# Qiao.net
KiCad netlist of a schematic drawn in Altium Designer
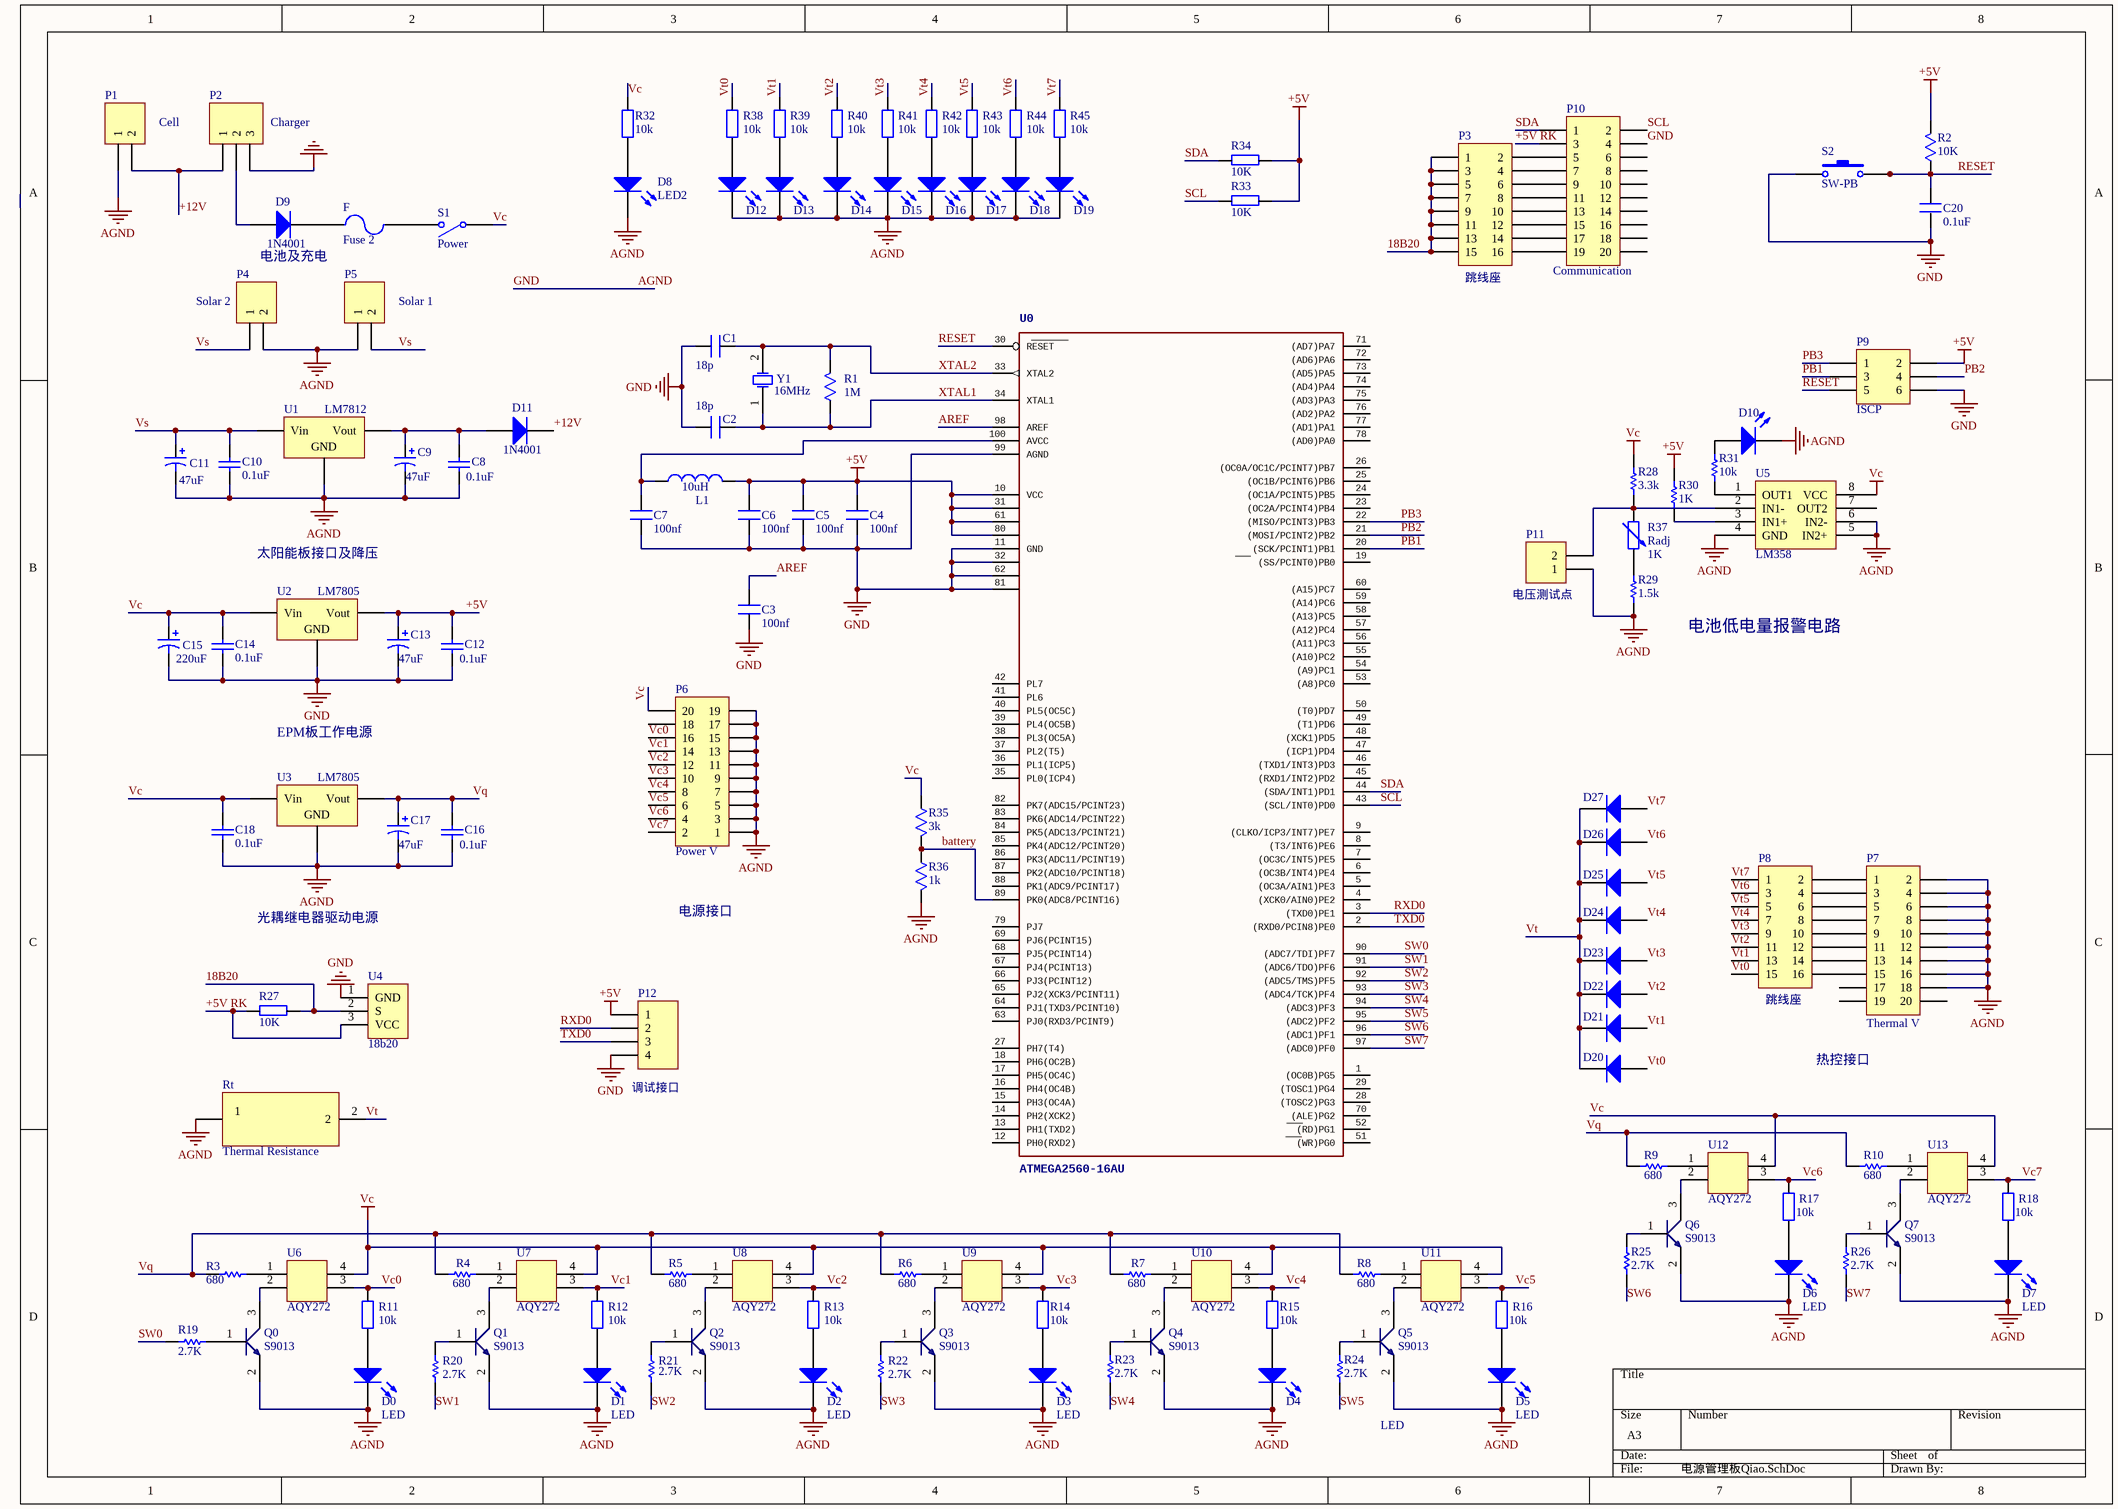
[diagram p0: 电源管理板Qiao.SchDoc]

(export (version "E")
  (design (tool "Eeschema 10.0.6"))
  (components
    (comp (ref "C1") (value "18p") (footprint "CAPC3216M") (libsource (lib "STM32封装库") (part "C_1")))
    (comp (ref "C2") (value "18p") (footprint "CAPC3216M") (libsource (lib "STM32封装库") (part "C_1")))
    (comp (ref "C3") (value "100nf") (footprint "CAPC3216M") (libsource (lib "STM32封装库") (part "C")))
    (comp (ref "C4") (value "100nf") (footprint "CAPC3216M") (libsource (lib "STM32封装库") (part "C")))
    (comp (ref "C5") (value "100nf") (footprint "CAPC3216M") (libsource (lib "STM32封装库") (part "C")))
    (comp (ref "C6") (value "100nf") (footprint "CAPC3216M") (libsource (lib "STM32封装库") (part "C")))
    (comp (ref "C7") (value "100nf") (footprint "CAPC3216M") (libsource (lib "STM32封装库") (part "C")))
    (comp (ref "C8")
      (value "0.1uF")
      (footprint "CAPC3216M")
      (description "0.1uf")
      (fields (field (name "PUBLISHER") "Altium Limited"))
      (libsource (lib "Miscellaneous Devices") (part "Cap Semi"))
    )
    (comp (ref "C9")
      (value "47uF")
      (footprint "25V47uF")
      (description "47uf")
      (fields (field (name "Comment") "25V47uF") (field (name "PUBLISHER") "Altium Limited"))
      (libsource (lib "Miscellaneous Devices") (part "Cap Pol3"))
    )
    (comp (ref "C10")
      (value "0.1uF")
      (footprint "CAPC3216M")
      (description "0.1uf")
      (fields (field (name "PUBLISHER") "Altium Limited"))
      (libsource (lib "电源管理板") (part "Cap"))
    )
    (comp (ref "C11")
      (value "47uF")
      (footprint "25V47uF")
      (description "47uf")
      (fields (field (name "Comment") "25V47uF") (field (name "PUBLISHER") "Altium Limited"))
      (libsource (lib "Miscellaneous Devices") (part "Cap Pol3"))
    )
    (comp (ref "C12")
      (value "0.1uF")
      (footprint "CAPC3216M")
      (description "0.1uf")
      (fields (field (name "PUBLISHER") "Altium Limited"))
      (libsource (lib "Miscellaneous Devices") (part "Cap Semi"))
    )
    (comp (ref "C13")
      (value "47uF")
      (footprint "25V47uF")
      (description "10uf")
      (fields (field (name "Comment") "25V47uF") (field (name "PUBLISHER") "Altium Limited"))
      (libsource (lib "Miscellaneous Devices") (part "Cap Pol3"))
    )
    (comp (ref "C14")
      (value "0.1uF")
      (footprint "CAPC3216M")
      (description "0.1uf")
      (fields (field (name "PUBLISHER") "Altium Limited"))
      (libsource (lib "Miscellaneous Devices") (part "Cap"))
    )
    (comp (ref "C15")
      (value "220uF")
      (footprint "25V47uF")
      (description "10uf")
      (fields (field (name "Comment") "50V220uF") (field (name "PUBLISHER") "Altium Limited"))
      (libsource (lib "Miscellaneous Devices") (part "Cap Pol3"))
    )
    (comp (ref "C16")
      (value "0.1uF")
      (footprint "CAPC3216M")
      (description "0.1uf")
      (fields (field (name "PUBLISHER") "Altium Limited"))
      (libsource (lib "Miscellaneous Devices") (part "Cap Semi"))
    )
    (comp (ref "C17")
      (value "47uF")
      (footprint "25V47uF")
      (description "10uf")
      (fields (field (name "Comment") "25V47uF") (field (name "PUBLISHER") "Altium Limited"))
      (libsource (lib "Miscellaneous Devices") (part "Cap Pol3"))
    )
    (comp (ref "C18")
      (value "0.1uF")
      (footprint "CAPC3216M")
      (description "0.1uf")
      (fields (field (name "PUBLISHER") "Altium Limited"))
      (libsource (lib "Miscellaneous Devices") (part "Cap"))
    )
    (comp (ref "C20") (value "0.1uF") (footprint "CAPC3216M") (libsource (lib "STM32封装库") (part "C_3")))
    (comp (ref "D0")
      (value "LED")
      (footprint "LED")
      (description "Typical RED, GREEN, YELLOW, AMBER GaAs LED")
      (fields (field (name "PUBLISHER") "Altium Limited"))
      (libsource (lib "Miscellaneous Devices") (part "LED2"))
    )
    (comp (ref "D1")
      (value "LED")
      (footprint "LED")
      (description "Typical RED, GREEN, YELLOW, AMBER GaAs LED")
      (fields (field (name "PUBLISHER") "Altium Limited"))
      (libsource (lib "Miscellaneous Devices") (part "LED2"))
    )
    (comp (ref "D2")
      (value "LED")
      (footprint "LED")
      (description "Typical RED, GREEN, YELLOW, AMBER GaAs LED")
      (fields (field (name "PUBLISHER") "Altium Limited"))
      (libsource (lib "Miscellaneous Devices") (part "LED2"))
    )
    (comp (ref "D3")
      (value "LED")
      (footprint "LED")
      (description "Typical RED, GREEN, YELLOW, AMBER GaAs LED")
      (fields (field (name "PUBLISHER") "Altium Limited"))
      (libsource (lib "Miscellaneous Devices") (part "LED2"))
    )
    (comp (ref "D4")
      (value "LED")
      (footprint "LED")
      (description "Typical RED, GREEN, YELLOW, AMBER GaAs LED")
      (fields (field (name "PUBLISHER") "Altium Limited"))
      (libsource (lib "Miscellaneous Devices") (part "LED2"))
    )
    (comp (ref "D5")
      (value "LED")
      (footprint "LED")
      (description "Typical RED, GREEN, YELLOW, AMBER GaAs LED")
      (fields (field (name "PUBLISHER") "Altium Limited"))
      (libsource (lib "Miscellaneous Devices") (part "LED2"))
    )
    (comp (ref "D6")
      (value "LED")
      (footprint "LED")
      (description "Typical RED, GREEN, YELLOW, AMBER GaAs LED")
      (fields (field (name "PUBLISHER") "Altium Limited"))
      (libsource (lib "Miscellaneous Devices") (part "LED2"))
    )
    (comp (ref "D7")
      (value "LED")
      (footprint "LED")
      (description "Typical RED, GREEN, YELLOW, AMBER GaAs LED")
      (fields (field (name "PUBLISHER") "Altium Limited"))
      (libsource (lib "Miscellaneous Devices") (part "LED2"))
    )
    (comp (ref "D8")
      (value "LED2")
      (footprint "DIPLED")
      (description "Typical RED, GREEN, YELLOW, AMBER GaAs LED")
      (fields (field (name "PUBLISHER") "Altium Limited"))
      (libsource (lib "Miscellaneous Devices") (part "LED2"))
    )
    (comp (ref "D9")
      (value "1N4001")
      (footprint "SMB")
      (description "1 Amp General Purpose Rectifier")
      (fields (field (name "PUBLISHER") "Altium Limited"))
      (libsource (lib "Miscellaneous Devices") (part "Diode 1N4001"))
    )
    (comp (ref "D10") (value "LED") (footprint "DIPLED") (libsource (lib "常用元件库") (part "LED")))
    (comp (ref "D11")
      (value "1N4001")
      (footprint "SMB")
      (description "1 Amp General Purpose Rectifier")
      (fields (field (name "PUBLISHER") "Altium Limited"))
      (libsource (lib "Miscellaneous Devices") (part "Diode 1N4001"))
    )
    (comp (ref "D12")
      (value "LED")
      (footprint "LED")
      (description "Typical RED, GREEN, YELLOW, AMBER GaAs LED")
      (fields (field (name "PUBLISHER") "Altium Limited"))
      (libsource (lib "Miscellaneous Devices") (part "LED2"))
    )
    (comp (ref "D13")
      (value "LED")
      (footprint "LED")
      (description "Typical RED, GREEN, YELLOW, AMBER GaAs LED")
      (fields (field (name "PUBLISHER") "Altium Limited"))
      (libsource (lib "Miscellaneous Devices") (part "LED2"))
    )
    (comp (ref "D14")
      (value "LED")
      (footprint "LED")
      (description "Typical RED, GREEN, YELLOW, AMBER GaAs LED")
      (fields (field (name "PUBLISHER") "Altium Limited"))
      (libsource (lib "Miscellaneous Devices") (part "LED2"))
    )
    (comp (ref "D15")
      (value "LED")
      (footprint "LED")
      (description "Typical RED, GREEN, YELLOW, AMBER GaAs LED")
      (fields (field (name "PUBLISHER") "Altium Limited"))
      (libsource (lib "Miscellaneous Devices") (part "LED2"))
    )
    (comp (ref "D16")
      (value "LED")
      (footprint "LED")
      (description "Typical RED, GREEN, YELLOW, AMBER GaAs LED")
      (fields (field (name "PUBLISHER") "Altium Limited"))
      (libsource (lib "Miscellaneous Devices") (part "LED2"))
    )
    (comp (ref "D17")
      (value "LED")
      (footprint "LED")
      (description "Typical RED, GREEN, YELLOW, AMBER GaAs LED")
      (fields (field (name "PUBLISHER") "Altium Limited"))
      (libsource (lib "Miscellaneous Devices") (part "LED2"))
    )
    (comp (ref "D18")
      (value "LED")
      (footprint "LED")
      (description "Typical RED, GREEN, YELLOW, AMBER GaAs LED")
      (fields (field (name "PUBLISHER") "Altium Limited"))
      (libsource (lib "Miscellaneous Devices") (part "LED2"))
    )
    (comp (ref "D19")
      (value "LED")
      (footprint "LED")
      (description "Typical RED, GREEN, YELLOW, AMBER GaAs LED")
      (fields (field (name "PUBLISHER") "Altium Limited"))
      (libsource (lib "Miscellaneous Devices") (part "LED2"))
    )
    (comp (ref "D20")
      (value "1N4001")
      (footprint "SMB")
      (description "1 Amp General Purpose Rectifier")
      (fields (field (name "PUBLISHER") "Altium Limited"))
      (libsource (lib "Miscellaneous Devices") (part "Diode 1N4001"))
    )
    (comp (ref "D21")
      (value "1N4001")
      (footprint "SMB")
      (description "1 Amp General Purpose Rectifier")
      (fields (field (name "PUBLISHER") "Altium Limited"))
      (libsource (lib "Miscellaneous Devices") (part "Diode 1N4001"))
    )
    (comp (ref "D22")
      (value "1N4001")
      (footprint "SMB")
      (description "1 Amp General Purpose Rectifier")
      (fields (field (name "PUBLISHER") "Altium Limited"))
      (libsource (lib "Miscellaneous Devices") (part "Diode 1N4001"))
    )
    (comp (ref "D23")
      (value "1N4001")
      (footprint "SMB")
      (description "1 Amp General Purpose Rectifier")
      (fields (field (name "PUBLISHER") "Altium Limited"))
      (libsource (lib "Miscellaneous Devices") (part "Diode 1N4001"))
    )
    (comp (ref "D24")
      (value "1N4001")
      (footprint "SMB")
      (description "1 Amp General Purpose Rectifier")
      (fields (field (name "PUBLISHER") "Altium Limited"))
      (libsource (lib "Miscellaneous Devices") (part "Diode 1N4001"))
    )
    (comp (ref "D25")
      (value "1N4001")
      (footprint "SMB")
      (description "1 Amp General Purpose Rectifier")
      (fields (field (name "PUBLISHER") "Altium Limited"))
      (libsource (lib "Miscellaneous Devices") (part "Diode 1N4001"))
    )
    (comp (ref "D26")
      (value "1N4001")
      (footprint "SMB")
      (description "1 Amp General Purpose Rectifier")
      (fields (field (name "PUBLISHER") "Altium Limited"))
      (libsource (lib "Miscellaneous Devices") (part "Diode 1N4001"))
    )
    (comp (ref "D27")
      (value "1N4001")
      (footprint "SMB")
      (description "1 Amp General Purpose Rectifier")
      (fields (field (name "PUBLISHER") "Altium Limited"))
      (libsource (lib "Miscellaneous Devices") (part "Diode 1N4001"))
    )
    (comp (ref "F")
      (value "Fuse 2")
      (footprint "1812")
      (description "Fuse")
      (fields (field (name "PUBLISHER") "Altium Limited"))
      (libsource (lib "Miscellaneous Devices") (part "Fuse 2"))
    )
    (comp (ref "L1")
      (value "10uH")
      (footprint "CAPC3216M")
      (description "Inductor")
      (fields (field (name "PUBLISHER") "Altium Limited"))
      (libsource (lib "Miscellaneous Devices") (part "Inductor"))
    )
    (comp (ref "P1")
      (value "Cell")
      (footprint "2P3.96wanzhenzuo")
      (description "Header, 2-Pin")
      (fields (field (name "PUBLISHER") "Altium Limited"))
      (libsource (lib "Miscellaneous Connectors") (part "Header 2"))
    )
    (comp (ref "P2")
      (value "Charger")
      (footprint "ChargeSocket")
      (description "Header, 3-Pin")
      (fields (field (name "PUBLISHER") "Altium Limited"))
      (libsource (lib "Miscellaneous Connectors") (part "Header 3"))
    )
    (comp (ref "P3")
      (value "跳线座")
      (footprint "HDR2X8")
      (description "Header, 8-Pin, Dual row")
      (fields (field (name "PUBLISHER") "Altium Limited"))
      (libsource (lib "Miscellaneous Connectors") (part "Header 8X2"))
    )
    (comp (ref "P4")
      (value "Solar 2")
      (footprint "2P3.96wanzhenzuo")
      (description "Header, 2-Pin")
      (fields (field (name "PUBLISHER") "Altium Limited"))
      (libsource (lib "Miscellaneous Connectors") (part "Header 2"))
    )
    (comp (ref "P5")
      (value "Solar 1")
      (footprint "2P3.96wanzhenzuo")
      (description "Header, 2-Pin")
      (fields (field (name "PUBLISHER") "Altium Limited"))
      (libsource (lib "Miscellaneous Connectors") (part "Header 2"))
    )
    (comp (ref "P6")
      (value "Power V")
      (footprint "HDR2X10")
      (description "Header, 10-Pin, Dual row")
      (fields (field (name "PUBLISHER") "Altium Limited"))
      (libsource (lib "Miscellaneous Connectors") (part "Header 10X2"))
    )
    (comp (ref "P7")
      (value "Thermal V")
      (footprint "HDR2X10")
      (description "Header, 10-Pin, Dual row")
      (fields (field (name "PUBLISHER") "Altium Limited"))
      (libsource (lib "") (part "Header 10X2_1"))
    )
    (comp (ref "P8")
      (value "跳线座")
      (footprint "HDR2X8")
      (description "Header, 8-Pin, Dual row")
      (fields (field (name "PUBLISHER") "Altium Limited"))
      (libsource (lib "Miscellaneous Connectors") (part "Header 8X2"))
    )
    (comp (ref "P9")
      (value "ISCP")
      (footprint "HDR2X3")
      (description "Header, 3-Pin, Dual row")
      (fields (field (name "PUBLISHER") "Altium Limited"))
      (libsource (lib "Miscellaneous Connectors") (part "Header 3X2"))
    )
    (comp (ref "P10")
      (value "Communication")
      (footprint "HDR2X10")
      (description "Header, 10-Pin, Dual row")
      (fields (field (name "PUBLISHER") "Altium Limited"))
      (libsource (lib "") (part "Header 10X2_1"))
    )
    (comp (ref "P11")
      (value "电压测试点")
      (footprint "HDR1X2")
      (description "Header, 2-Pin")
      (fields (field (name "PUBLISHER") "Altium Limited"))
      (libsource (lib "") (part "Header 2_1"))
    )
    (comp (ref "P12")
      (value "调试接口")
      (footprint "HDR1X4")
      (description "Header, 4-Pin")
      (fields (field (name "PUBLISHER") "Altium Limited"))
      (libsource (lib "Miscellaneous Connectors") (part "Header 4"))
    )
    (comp (ref "Q0") (value "S9013") (footprint "SOT23") (libsource (lib "常用元件库") (part "S9013")))
    (comp (ref "Q1") (value "S9013") (footprint "sot23") (libsource (lib "常用元件库") (part "S9013")))
    (comp (ref "Q2") (value "S9013") (footprint "sot23") (libsource (lib "常用元件库") (part "S9013")))
    (comp (ref "Q3") (value "S9013") (footprint "sot23") (libsource (lib "常用元件库") (part "S9013")))
    (comp (ref "Q4") (value "S9013") (footprint "sot23") (libsource (lib "常用元件库") (part "S9013")))
    (comp (ref "Q5") (value "S9013") (footprint "sot23") (libsource (lib "常用元件库") (part "S9013")))
    (comp (ref "Q6") (value "S9013") (footprint "sot23") (libsource (lib "常用元件库") (part "S9013")))
    (comp (ref "Q7") (value "S9013") (footprint "sot23") (libsource (lib "常用元件库") (part "S9013")))
    (comp (ref "R1") (value "1M") (footprint "RESC3216M") (libsource (lib "YT1_SCH_99SE") (part "RES")))
    (comp (ref "R2") (value "10K") (footprint "RESC3216M") (libsource (lib "YT1_SCH_99SE") (part "RES")))
    (comp (ref "R3")
      (value "680")
      (footprint "RESC3216M")
      (description "resistance")
      (libsource (lib "Sat_Integrated_Library") (part "Res"))
    )
    (comp (ref "R4")
      (value "680")
      (footprint "RESC3216M")
      (description "resistance")
      (libsource (lib "Sat_Integrated_Library") (part "Res"))
    )
    (comp (ref "R5")
      (value "680")
      (footprint "RESC3216M")
      (description "resistance")
      (libsource (lib "Sat_Integrated_Library") (part "Res"))
    )
    (comp (ref "R6")
      (value "680")
      (footprint "RESC3216M")
      (description "resistance")
      (libsource (lib "Sat_Integrated_Library") (part "Res"))
    )
    (comp (ref "R7")
      (value "680")
      (footprint "RESC3216M")
      (description "resistance")
      (libsource (lib "Sat_Integrated_Library") (part "Res"))
    )
    (comp (ref "R8")
      (value "680")
      (footprint "RESC3216M")
      (description "resistance")
      (libsource (lib "Sat_Integrated_Library") (part "Res"))
    )
    (comp (ref "R9")
      (value "680")
      (footprint "RESC3216M")
      (description "resistance")
      (libsource (lib "Sat_Integrated_Library") (part "Res"))
    )
    (comp (ref "R10")
      (value "680")
      (footprint "RESC3216M")
      (description "resistance")
      (libsource (lib "Sat_Integrated_Library") (part "Res"))
    )
    (comp (ref "R11")
      (value "10k")
      (footprint "RESC3216M")
      (description "5.1k")
      (fields (field (name "Comment") "10K") (field (name "PUBLISHER") "Altium Limited"))
      (libsource (lib "Miscellaneous Devices") (part "Res2"))
    )
    (comp (ref "R12")
      (value "10k")
      (footprint "RESC3216M")
      (description "5.1k")
      (fields (field (name "Comment") "10K") (field (name "PUBLISHER") "Altium Limited"))
      (libsource (lib "Miscellaneous Devices") (part "Res2"))
    )
    (comp (ref "R13")
      (value "10k")
      (footprint "RESC3216M")
      (description "5.1k")
      (fields (field (name "Comment") "10K") (field (name "PUBLISHER") "Altium Limited"))
      (libsource (lib "Miscellaneous Devices") (part "Res2"))
    )
    (comp (ref "R14")
      (value "10k")
      (footprint "RESC3216M")
      (description "5.1k")
      (fields (field (name "Comment") "10K") (field (name "PUBLISHER") "Altium Limited"))
      (libsource (lib "Miscellaneous Devices") (part "Res2"))
    )
    (comp (ref "R15")
      (value "10k")
      (footprint "RESC3216M")
      (description "5.1k")
      (fields (field (name "Comment") "10K") (field (name "PUBLISHER") "Altium Limited"))
      (libsource (lib "Miscellaneous Devices") (part "Res2"))
    )
    (comp (ref "R16")
      (value "10k")
      (footprint "RESC3216M")
      (description "5.1k")
      (fields (field (name "Comment") "10K") (field (name "PUBLISHER") "Altium Limited"))
      (libsource (lib "Miscellaneous Devices") (part "Res2"))
    )
    (comp (ref "R17")
      (value "10k")
      (footprint "RESC3216M")
      (description "5.1k")
      (fields (field (name "Comment") "10K") (field (name "PUBLISHER") "Altium Limited"))
      (libsource (lib "Miscellaneous Devices") (part "Res2"))
    )
    (comp (ref "R18")
      (value "10k")
      (footprint "RESC3216M")
      (description "5.1k")
      (fields (field (name "Comment") "10K") (field (name "PUBLISHER") "Altium Limited"))
      (libsource (lib "Miscellaneous Devices") (part "Res2"))
    )
    (comp (ref "R19")
      (value "2.7K")
      (footprint "RESC3216M")
      (description "resistance")
      (libsource (lib "Sat_Integrated_Library") (part "Res"))
    )
    (comp (ref "R20")
      (value "2.7K")
      (footprint "RESC3216M")
      (description "resistance")
      (libsource (lib "Sat_Integrated_Library") (part "Res"))
    )
    (comp (ref "R21")
      (value "2.7K")
      (footprint "RESC3216M")
      (description "resistance")
      (libsource (lib "Sat_Integrated_Library") (part "Res"))
    )
    (comp (ref "R22")
      (value "2.7K")
      (footprint "RESC3216M")
      (description "resistance")
      (libsource (lib "Sat_Integrated_Library") (part "Res"))
    )
    (comp (ref "R23")
      (value "2.7K")
      (footprint "RESC3216M")
      (description "resistance")
      (libsource (lib "Sat_Integrated_Library") (part "Res"))
    )
    (comp (ref "R24")
      (value "2.7K")
      (footprint "RESC3216M")
      (description "resistance")
      (libsource (lib "Sat_Integrated_Library") (part "Res"))
    )
    (comp (ref "R25")
      (value "2.7K")
      (footprint "RESC3216M")
      (description "resistance")
      (libsource (lib "Sat_Integrated_Library") (part "Res"))
    )
    (comp (ref "R26")
      (value "2.7K")
      (footprint "RESC3216M")
      (description "resistance")
      (libsource (lib "Sat_Integrated_Library") (part "Res"))
    )
    (comp (ref "R27") (value "10K") (footprint "RESC3216M") (libsource (lib "STM32封装库") (part "R")))
    (comp (ref "R28")
      (value "3.3k")
      (footprint "CAPC3216M")
      (description "resistance")
      (libsource (lib "Sat_Integrated_Library") (part "Res"))
    )
    (comp (ref "R29")
      (value "1.5k")
      (footprint "CAPC3216M")
      (description "resistance")
      (libsource (lib "Sat_Integrated_Library") (part "Res"))
    )
    (comp (ref "R30")
      (value "1K")
      (footprint "CAPC3216M")
      (description "resistance")
      (libsource (lib "Sat_Integrated_Library") (part "Res"))
    )
    (comp (ref "R31")
      (value "10k")
      (footprint "CAPC3216M")
      (description "resistance")
      (libsource (lib "Sat_Integrated_Library") (part "Res"))
    )
    (comp (ref "R32")
      (value "10k")
      (footprint "RESC3216M")
      (description "5.1k")
      (fields (field (name "PUBLISHER") "Altium Limited"))
      (libsource (lib "Miscellaneous Devices") (part "Res2"))
    )
    (comp (ref "R33") (value "10K") (footprint "RESC3216M") (libsource (lib "STM32封装库") (part "R")))
    (comp (ref "R34") (value "10K") (footprint "RESC3216M") (libsource (lib "STM32封装库") (part "R")))
    (comp (ref "R35") (value "3k") (footprint "RESC3216M") (libsource (lib "YT1_SCH_99SE") (part "RES")))
    (comp (ref "R36") (value "1k") (footprint "RESC3216M") (libsource (lib "YT1_SCH_99SE") (part "RES")))
    (comp (ref "R37")
      (value "Radj")
      (footprint "ResAdj")
      (description "Variable Resistor")
      (fields (field (name "ALTIUM_VALUE") "1K") (field (name "PUBLISHER") "Altium Limited"))
      (libsource (lib "Miscellaneous Devices") (part "Res Adj2"))
    )
    (comp (ref "R38")
      (value "10k")
      (footprint "RESC3216M")
      (description "5.1k")
      (fields (field (name "Comment") "10K") (field (name "PUBLISHER") "Altium Limited"))
      (libsource (lib "Miscellaneous Devices") (part "Res2"))
    )
    (comp (ref "R39")
      (value "10k")
      (footprint "RESC3216M")
      (description "5.1k")
      (fields (field (name "Comment") "10K") (field (name "PUBLISHER") "Altium Limited"))
      (libsource (lib "Miscellaneous Devices") (part "Res2"))
    )
    (comp (ref "R40")
      (value "10k")
      (footprint "RESC3216M")
      (description "5.1k")
      (fields (field (name "Comment") "10K") (field (name "PUBLISHER") "Altium Limited"))
      (libsource (lib "Miscellaneous Devices") (part "Res2"))
    )
    (comp (ref "R41")
      (value "10k")
      (footprint "RESC3216M")
      (description "5.1k")
      (fields (field (name "Comment") "10K") (field (name "PUBLISHER") "Altium Limited"))
      (libsource (lib "Miscellaneous Devices") (part "Res2"))
    )
    (comp (ref "R42")
      (value "10k")
      (footprint "RESC3216M")
      (description "5.1k")
      (fields (field (name "Comment") "10K") (field (name "PUBLISHER") "Altium Limited"))
      (libsource (lib "Miscellaneous Devices") (part "Res2"))
    )
    (comp (ref "R43")
      (value "10k")
      (footprint "RESC3216M")
      (description "5.1k")
      (fields (field (name "Comment") "10K") (field (name "PUBLISHER") "Altium Limited"))
      (libsource (lib "Miscellaneous Devices") (part "Res2"))
    )
    (comp (ref "R44")
      (value "10k")
      (footprint "RESC3216M")
      (description "5.1k")
      (fields (field (name "Comment") "10K") (field (name "PUBLISHER") "Altium Limited"))
      (libsource (lib "Miscellaneous Devices") (part "Res2"))
    )
    (comp (ref "R45")
      (value "10k")
      (footprint "RESC3216M")
      (description "5.1k")
      (fields (field (name "Comment") "10K") (field (name "PUBLISHER") "Altium Limited"))
      (libsource (lib "Miscellaneous Devices") (part "Res2"))
    )
    (comp (ref "Rt")
      (value "Thermal Resistance")
      (footprint "Thermal Res")
      (libsource (lib "MyFootprintLibrary") (part "ThermalResistance"))
    )
    (comp (ref "S1")
      (value "Power")
      (footprint "PWRSWITCH")
      (description "Single-Pole, Single-Throw Switch")
      (fields (field (name "PUBLISHER") "Altium Limited"))
      (libsource (lib "Miscellaneous Devices") (part "SW-SPST"))
    )
    (comp (ref "S2")
      (value "SW-PB")
      (footprint "PUSH BUTTON 6x6")
      (description "Switch")
      (fields (field (name "PUBLISHER") "Altium Limited"))
      (libsource (lib "Miscellaneous Devices") (part "SW-PB"))
    )
    (comp (ref "U0")
      (value "ATMEGA2560-16AU")
      (footprint "TQFP100")
      (libsource (lib "Arduino_MEGA_2560-Rev3") (part "ATMEGA2560AU"))
    )
    (comp (ref "U1")
      (value "LM7812")
      (footprint "DPAK-3")
      (description "Voltage Regulator")
      (fields (field (name "PUBLISHER") "Altium Limited"))
      (libsource (lib "Miscellaneous Devices") (part "Volt Reg"))
    )
    (comp (ref "U2")
      (value "LM7805")
      (footprint "DPAK-3")
      (description "Voltage Regulator")
      (fields (field (name "PUBLISHER") "Altium Limited"))
      (libsource (lib "Miscellaneous Devices") (part "Volt Reg"))
    )
    (comp (ref "U3")
      (value "LM7805")
      (footprint "DPAK-3")
      (description "Voltage Regulator")
      (fields (field (name "PUBLISHER") "Altium Limited"))
      (libsource (lib "Miscellaneous Devices") (part "Volt Reg"))
    )
    (comp (ref "U4") (value "18b20") (footprint "TO92") (libsource (lib "常用元件库") (part "18b20")))
    (comp (ref "U5") (value "LM358") (footprint "SO-8") (libsource (lib "常用元件库") (part "LM358")))
    (comp (ref "U6")
      (value "AQY272")
      (footprint "AQY272")
      (libsource (lib "Sat_Integrated_Library") (part "AQY272"))
    )
    (comp (ref "U7")
      (value "AQY272")
      (footprint "AQY272")
      (libsource (lib "Sat_Integrated_Library") (part "AQY272"))
    )
    (comp (ref "U8")
      (value "AQY272")
      (footprint "AQY272")
      (libsource (lib "Sat_Integrated_Library") (part "AQY272"))
    )
    (comp (ref "U9")
      (value "AQY272")
      (footprint "AQY272")
      (libsource (lib "Sat_Integrated_Library") (part "AQY272"))
    )
    (comp (ref "U10")
      (value "AQY272")
      (footprint "AQY272")
      (libsource (lib "Sat_Integrated_Library") (part "AQY272"))
    )
    (comp (ref "U11")
      (value "AQY272")
      (footprint "AQY272")
      (libsource (lib "Sat_Integrated_Library") (part "AQY272"))
    )
    (comp (ref "U12")
      (value "AQY272")
      (footprint "AQY272")
      (libsource (lib "Sat_Integrated_Library") (part "AQY272"))
    )
    (comp (ref "U13")
      (value "AQY272")
      (footprint "电源管理板:AQY272")
      (libsource (lib "Sat_Integrated_Library") (part "AQY272"))
    )
    (comp (ref "Y1")
      (value "16MHz")
      (footprint "XTAL_US")
      (description "Crystal Oscillator")
      (fields (field (name "PUBLISHER") "Altium Limited"))
      (libsource (lib "电源管理板") (part "XTAL"))
    )
  )
  (nets
    (net (code "1") (name "+5V") (class "Default")
      (node (ref "C12") (pin "2") (pinfunction "2_2") (pintype "passive"))
      (node (ref "C13") (pin "1") (pinfunction "1_1") (pintype "passive"))
      (node (ref "C4") (pin "2") (pintype "passive"))
      (node (ref "C5") (pin "2") (pintype "passive"))
      (node (ref "C6") (pin "2") (pintype "passive"))
      (node (ref "L1") (pin "2") (pinfunction "2_2") (pintype "passive"))
      (node (ref "P12") (pin "1") (pinfunction "1_1") (pintype "passive"))
      (node (ref "P9") (pin "2") (pinfunction "2_2") (pintype "passive"))
      (node (ref "R2") (pin "2") (pinfunction "2_2") (pintype "passive"))
      (node (ref "R30") (pin "2") (pinfunction "2_2") (pintype "passive"))
      (node (ref "R33") (pin "1") (pintype "passive"))
      (node (ref "R34") (pin "1") (pintype "passive"))
      (node (ref "U0") (pin "10") (pinfunction "VCC_10") (pintype "power_in"))
      (node (ref "U0") (pin "31") (pinfunction "VCC1_31") (pintype "power_in"))
      (node (ref "U0") (pin "61") (pinfunction "VCC2_61") (pintype "power_in"))
      (node (ref "U0") (pin "80") (pinfunction "VCC3_80") (pintype "power_in"))
      (node (ref "U2") (pin "3") (pinfunction "Vout_3") (pintype "passive"))
    )
    (net (code "2") (name "/+5V RK") (class "Default")
      (node (ref "P10") (pin "3") (pinfunction "3_3") (pintype "passive"))
      (node (ref "R27") (pin "2") (pintype "passive"))
      (node (ref "U4") (pin "3") (pinfunction "VCC_3") (pintype "passive"))
    )
    (net (code "3") (name "/+12V") (class "Default")
      (node (ref "D11") (pin "2") (pinfunction "K_2") (pintype "passive"))
      (node (ref "P1") (pin "2") (pinfunction "2_2") (pintype "passive"))
      (node (ref "P2") (pin "1") (pinfunction "1_1") (pintype "passive"))
    )
    (net (code "4") (name "/18B20") (class "Default")
      (node (ref "P3") (pin "1") (pinfunction "1_1") (pintype "passive"))
      (node (ref "P3") (pin "11") (pinfunction "11_11") (pintype "passive"))
      (node (ref "P3") (pin "13") (pinfunction "13_13") (pintype "passive"))
      (node (ref "P3") (pin "15") (pinfunction "15_15") (pintype "passive"))
      (node (ref "P3") (pin "3") (pinfunction "3_3") (pintype "passive"))
      (node (ref "P3") (pin "5") (pinfunction "5_5") (pintype "passive"))
      (node (ref "P3") (pin "7") (pinfunction "7_7") (pintype "passive"))
      (node (ref "P3") (pin "9") (pinfunction "9_9") (pintype "passive"))
      (node (ref "R27") (pin "1") (pintype "passive"))
      (node (ref "U4") (pin "2") (pinfunction "S_2") (pintype "passive"))
    )
    (net (code "5") (name "/AREF") (class "Default")
      (node (ref "C3") (pin "2") (pintype "passive"))
      (node (ref "U0") (pin "98") (pinfunction "AREF_98") (pintype "passive"))
    )
    (net (code "6") (name "/PB1") (class "Default")
      (node (ref "P9") (pin "3") (pinfunction "3_3") (pintype "passive"))
      (node (ref "U0") (pin "20") (pinfunction "(SCK/PCINT1)PB1_20") (pintype "passive"))
    )
    (net (code "7") (name "/PB2") (class "Default")
      (node (ref "P9") (pin "4") (pinfunction "4_4") (pintype "passive"))
      (node (ref "U0") (pin "21") (pinfunction "(MOSI/PCINT2)PB2_21") (pintype "passive"))
    )
    (net (code "8") (name "/PB3") (class "Default")
      (node (ref "P9") (pin "1") (pinfunction "1_1") (pintype "passive"))
      (node (ref "U0") (pin "22") (pinfunction "(MISO/PCINT3)PB3_22") (pintype "passive"))
    )
    (net (code "9") (name "/RESET") (class "Default")
      (node (ref "C20") (pin "2") (pintype "passive"))
      (node (ref "P9") (pin "5") (pinfunction "5_5") (pintype "passive"))
      (node (ref "R2") (pin "1") (pinfunction "1_1") (pintype "passive"))
      (node (ref "S2") (pin "2") (pinfunction "2_2") (pintype "passive"))
      (node (ref "U0") (pin "30") (pinfunction "RESET_30") (pintype "passive"))
    )
    (net (code "10") (name "/RXD0") (class "Default")
      (node (ref "P12") (pin "2") (pinfunction "2_2") (pintype "passive"))
      (node (ref "U0") (pin "3") (pinfunction "(TXD0)PE1_3") (pintype "passive"))
    )
    (net (code "11") (name "/SCL") (class "Default")
      (node (ref "P10") (pin "2") (pinfunction "2_2") (pintype "passive"))
      (node (ref "R33") (pin "2") (pintype "passive"))
      (node (ref "U0") (pin "43") (pinfunction "(SCL/INT0)PD0_43") (pintype "passive"))
    )
    (net (code "12") (name "/SDA") (class "Default")
      (node (ref "P10") (pin "1") (pinfunction "1_1") (pintype "passive"))
      (node (ref "R34") (pin "2") (pintype "passive"))
      (node (ref "U0") (pin "44") (pinfunction "(SDA/INT1)PD1_44") (pintype "passive"))
    )
    (net (code "13") (name "/SW0") (class "Default")
      (node (ref "R19") (pin "1") (pinfunction "1_1") (pintype "passive"))
      (node (ref "U0") (pin "90") (pinfunction "(ADC7/TDI)PF7_90") (pintype "passive"))
    )
    (net (code "14") (name "/SW1") (class "Default")
      (node (ref "R20") (pin "1") (pinfunction "1_1") (pintype "passive"))
      (node (ref "U0") (pin "91") (pinfunction "(ADC6/TDO)PF6_91") (pintype "passive"))
    )
    (net (code "15") (name "/SW2") (class "Default")
      (node (ref "R21") (pin "1") (pinfunction "1_1") (pintype "passive"))
      (node (ref "U0") (pin "92") (pinfunction "(ADC5/TMS)PF5_92") (pintype "passive"))
    )
    (net (code "16") (name "/SW3") (class "Default")
      (node (ref "R22") (pin "1") (pinfunction "1_1") (pintype "passive"))
      (node (ref "U0") (pin "93") (pinfunction "(ADC4/TCK)PF4_93") (pintype "passive"))
    )
    (net (code "17") (name "/SW4") (class "Default")
      (node (ref "R23") (pin "1") (pinfunction "1_1") (pintype "passive"))
      (node (ref "U0") (pin "94") (pinfunction "(ADC3)PF3_94") (pintype "passive"))
    )
    (net (code "18") (name "/SW5") (class "Default")
      (node (ref "R24") (pin "1") (pinfunction "1_1") (pintype "passive"))
      (node (ref "U0") (pin "95") (pinfunction "(ADC2)PF2_95") (pintype "passive"))
    )
    (net (code "19") (name "/SW6") (class "Default")
      (node (ref "R25") (pin "1") (pinfunction "1_1") (pintype "passive"))
      (node (ref "U0") (pin "96") (pinfunction "(ADC1)PF1_96") (pintype "passive"))
    )
    (net (code "20") (name "/SW7") (class "Default")
      (node (ref "R26") (pin "1") (pinfunction "1_1") (pintype "passive"))
      (node (ref "U0") (pin "97") (pinfunction "(ADC0)PF0_97") (pintype "passive"))
    )
    (net (code "21") (name "/TXD0") (class "Default")
      (node (ref "P12") (pin "3") (pinfunction "3_3") (pintype "passive"))
      (node (ref "U0") (pin "2") (pinfunction "(RXD0/PCIN8)PE0_2") (pintype "passive"))
    )
    (net (code "22") (name "/Vc0") (class "Default")
      (node (ref "P6") (pin "16") (pinfunction "16_16") (pintype "passive"))
      (node (ref "R11") (pin "2") (pinfunction "2_2") (pintype "passive"))
      (node (ref "U6") (pin "3") (pinfunction "3_3") (pintype "passive"))
    )
    (net (code "23") (name "/Vc1") (class "Default")
      (node (ref "P6") (pin "14") (pinfunction "14_14") (pintype "passive"))
      (node (ref "R12") (pin "2") (pinfunction "2_2") (pintype "passive"))
      (node (ref "U7") (pin "3") (pinfunction "3_3") (pintype "passive"))
    )
    (net (code "24") (name "/Vc2") (class "Default")
      (node (ref "P6") (pin "12") (pinfunction "12_12") (pintype "passive"))
      (node (ref "R13") (pin "2") (pinfunction "2_2") (pintype "passive"))
      (node (ref "U8") (pin "3") (pinfunction "3_3") (pintype "passive"))
    )
    (net (code "25") (name "/Vc3") (class "Default")
      (node (ref "P6") (pin "10") (pinfunction "10_10") (pintype "passive"))
      (node (ref "R14") (pin "2") (pinfunction "2_2") (pintype "passive"))
      (node (ref "U9") (pin "3") (pinfunction "3_3") (pintype "passive"))
    )
    (net (code "26") (name "/Vc4") (class "Default")
      (node (ref "P6") (pin "8") (pinfunction "8_8") (pintype "passive"))
      (node (ref "R15") (pin "2") (pinfunction "2_2") (pintype "passive"))
      (node (ref "U10") (pin "3") (pinfunction "3_3") (pintype "passive"))
    )
    (net (code "27") (name "/Vc5") (class "Default")
      (node (ref "P6") (pin "6") (pinfunction "6_6") (pintype "passive"))
      (node (ref "R16") (pin "2") (pinfunction "2_2") (pintype "passive"))
      (node (ref "U11") (pin "3") (pinfunction "3_3") (pintype "passive"))
    )
    (net (code "28") (name "/Vc6") (class "Default")
      (node (ref "P6") (pin "4") (pinfunction "4_4") (pintype "passive"))
      (node (ref "R17") (pin "2") (pinfunction "2_2") (pintype "passive"))
      (node (ref "U12") (pin "3") (pinfunction "3_3") (pintype "passive"))
    )
    (net (code "29") (name "/Vc7") (class "Default")
      (node (ref "P6") (pin "2") (pinfunction "2_2") (pintype "passive"))
      (node (ref "R18") (pin "2") (pinfunction "2_2") (pintype "passive"))
      (node (ref "U13") (pin "3") (pinfunction "3_3") (pintype "passive"))
    )
    (net (code "30") (name "/Vq") (class "Default")
      (node (ref "C16") (pin "2") (pinfunction "2_2") (pintype "passive"))
      (node (ref "C17") (pin "1") (pinfunction "1_1") (pintype "passive"))
      (node (ref "R10") (pin "1") (pinfunction "1_1") (pintype "passive"))
      (node (ref "R3") (pin "1") (pinfunction "1_1") (pintype "passive"))
      (node (ref "R4") (pin "1") (pinfunction "1_1") (pintype "passive"))
      (node (ref "R5") (pin "1") (pinfunction "1_1") (pintype "passive"))
      (node (ref "R6") (pin "1") (pinfunction "1_1") (pintype "passive"))
      (node (ref "R7") (pin "1") (pinfunction "1_1") (pintype "passive"))
      (node (ref "R8") (pin "1") (pinfunction "1_1") (pintype "passive"))
      (node (ref "R9") (pin "1") (pinfunction "1_1") (pintype "passive"))
      (node (ref "U3") (pin "3") (pinfunction "Vout_3") (pintype "passive"))
    )
    (net (code "31") (name "/Vs") (class "Default")
      (node (ref "C10") (pin "2") (pinfunction "2_2") (pintype "passive"))
      (node (ref "C11") (pin "1") (pinfunction "1_1") (pintype "passive"))
      (node (ref "P4") (pin "1") (pinfunction "1_1") (pintype "passive"))
      (node (ref "P5") (pin "2") (pinfunction "2_2") (pintype "passive"))
      (node (ref "U1") (pin "1") (pinfunction "Vin_1") (pintype "passive"))
    )
    (net (code "32") (name "/Vt") (class "Default")
      (node (ref "D20") (pin "2") (pinfunction "K_2") (pintype "passive"))
      (node (ref "D21") (pin "2") (pinfunction "K_2") (pintype "passive"))
      (node (ref "D22") (pin "2") (pinfunction "K_2") (pintype "passive"))
      (node (ref "D23") (pin "2") (pinfunction "K_2") (pintype "passive"))
      (node (ref "D24") (pin "2") (pinfunction "K_2") (pintype "passive"))
      (node (ref "D25") (pin "2") (pinfunction "K_2") (pintype "passive"))
      (node (ref "D26") (pin "2") (pinfunction "K_2") (pintype "passive"))
      (node (ref "D27") (pin "2") (pinfunction "K_2") (pintype "passive"))
      (node (ref "Rt") (pin "2") (pinfunction "2_2") (pintype "passive"))
    )
    (net (code "33") (name "/Vt0") (class "Default")
      (node (ref "D20") (pin "1") (pinfunction "A_1") (pintype "passive"))
      (node (ref "P8") (pin "15") (pinfunction "15_15") (pintype "passive"))
      (node (ref "R38") (pin "2") (pinfunction "2_2") (pintype "passive"))
    )
    (net (code "34") (name "/Vt1") (class "Default")
      (node (ref "D21") (pin "1") (pinfunction "A_1") (pintype "passive"))
      (node (ref "P8") (pin "13") (pinfunction "13_13") (pintype "passive"))
      (node (ref "R39") (pin "2") (pinfunction "2_2") (pintype "passive"))
    )
    (net (code "35") (name "/Vt2") (class "Default")
      (node (ref "D22") (pin "1") (pinfunction "A_1") (pintype "passive"))
      (node (ref "P8") (pin "11") (pinfunction "11_11") (pintype "passive"))
      (node (ref "R40") (pin "2") (pinfunction "2_2") (pintype "passive"))
    )
    (net (code "36") (name "/Vt3") (class "Default")
      (node (ref "D23") (pin "1") (pinfunction "A_1") (pintype "passive"))
      (node (ref "P8") (pin "9") (pinfunction "9_9") (pintype "passive"))
      (node (ref "R41") (pin "2") (pinfunction "2_2") (pintype "passive"))
    )
    (net (code "37") (name "/Vt4") (class "Default")
      (node (ref "D24") (pin "1") (pinfunction "A_1") (pintype "passive"))
      (node (ref "P8") (pin "7") (pinfunction "7_7") (pintype "passive"))
      (node (ref "R42") (pin "2") (pinfunction "2_2") (pintype "passive"))
    )
    (net (code "38") (name "/Vt5") (class "Default")
      (node (ref "D25") (pin "1") (pinfunction "A_1") (pintype "passive"))
      (node (ref "P8") (pin "5") (pinfunction "5_5") (pintype "passive"))
      (node (ref "R43") (pin "2") (pinfunction "2_2") (pintype "passive"))
    )
    (net (code "39") (name "/Vt6") (class "Default")
      (node (ref "D26") (pin "1") (pinfunction "A_1") (pintype "passive"))
      (node (ref "P8") (pin "3") (pinfunction "3_3") (pintype "passive"))
      (node (ref "R44") (pin "2") (pinfunction "2_2") (pintype "passive"))
    )
    (net (code "40") (name "/Vt7") (class "Default")
      (node (ref "D27") (pin "1") (pinfunction "A_1") (pintype "passive"))
      (node (ref "P8") (pin "1") (pinfunction "1_1") (pintype "passive"))
      (node (ref "R45") (pin "2") (pinfunction "2_2") (pintype "passive"))
    )
    (net (code "41") (name "/XTAL1") (class "Default")
      (node (ref "C2") (pin "2") (pintype "passive"))
      (node (ref "R1") (pin "1") (pinfunction "1_1") (pintype "passive"))
      (node (ref "U0") (pin "34") (pinfunction "XTAL1_34") (pintype "passive"))
      (node (ref "Y1") (pin "1") (pinfunction "OSC1_1") (pintype "passive"))
    )
    (net (code "42") (name "/XTAL2") (class "Default")
      (node (ref "C1") (pin "2") (pintype "passive"))
      (node (ref "R1") (pin "2") (pinfunction "2_2") (pintype "passive"))
      (node (ref "U0") (pin "33") (pinfunction "XTAL2_33") (pintype "output"))
      (node (ref "Y1") (pin "2") (pinfunction "OSC2_2") (pintype "passive"))
    )
    (net (code "43") (name "/battery") (class "Default")
      (node (ref "R35") (pin "2") (pinfunction "2_2") (pintype "passive"))
      (node (ref "R36") (pin "1") (pinfunction "1_1") (pintype "passive"))
      (node (ref "U0") (pin "89") (pinfunction "PK0(ADC8/PCINT16)_89") (pintype "passive"))
    )
    (net (code "44") (name "AGND") (class "Default")
      (node (ref "C1") (pin "1") (pintype "passive"))
      (node (ref "C10") (pin "1") (pinfunction "1_1") (pintype "passive"))
      (node (ref "C11") (pin "2") (pinfunction "2_2") (pintype "passive"))
      (node (ref "C12") (pin "1") (pinfunction "1_1") (pintype "passive"))
      (node (ref "C13") (pin "2") (pinfunction "2_2") (pintype "passive"))
      (node (ref "C14") (pin "1") (pinfunction "1_1") (pintype "passive"))
      (node (ref "C15") (pin "2") (pinfunction "2_2") (pintype "passive"))
      (node (ref "C16") (pin "1") (pinfunction "1_1") (pintype "passive"))
      (node (ref "C17") (pin "2") (pinfunction "2_2") (pintype "passive"))
      (node (ref "C18") (pin "1") (pinfunction "1_1") (pintype "passive"))
      (node (ref "C2") (pin "1") (pintype "passive"))
      (node (ref "C20") (pin "1") (pintype "passive"))
      (node (ref "C3") (pin "1") (pintype "passive"))
      (node (ref "C4") (pin "1") (pintype "passive"))
      (node (ref "C5") (pin "1") (pintype "passive"))
      (node (ref "C6") (pin "1") (pintype "passive"))
      (node (ref "C7") (pin "1") (pintype "passive"))
      (node (ref "C8") (pin "1") (pinfunction "1_1") (pintype "passive"))
      (node (ref "C9") (pin "2") (pinfunction "2_2") (pintype "passive"))
      (node (ref "D0") (pin "2") (pinfunction "K_2") (pintype "passive"))
      (node (ref "D1") (pin "2") (pinfunction "K_2") (pintype "passive"))
      (node (ref "D10") (pin "2") (pinfunction "K_2") (pintype "passive"))
      (node (ref "D12") (pin "2") (pinfunction "K_2") (pintype "passive"))
      (node (ref "D13") (pin "2") (pinfunction "K_2") (pintype "passive"))
      (node (ref "D14") (pin "2") (pinfunction "K_2") (pintype "passive"))
      (node (ref "D15") (pin "2") (pinfunction "K_2") (pintype "passive"))
      (node (ref "D16") (pin "2") (pinfunction "K_2") (pintype "passive"))
      (node (ref "D17") (pin "2") (pinfunction "K_2") (pintype "passive"))
      (node (ref "D18") (pin "2") (pinfunction "K_2") (pintype "passive"))
      (node (ref "D19") (pin "2") (pinfunction "K_2") (pintype "passive"))
      (node (ref "D2") (pin "2") (pinfunction "K_2") (pintype "passive"))
      (node (ref "D3") (pin "2") (pinfunction "K_2") (pintype "passive"))
      (node (ref "D4") (pin "2") (pinfunction "K_2") (pintype "passive"))
      (node (ref "D5") (pin "2") (pinfunction "K_2") (pintype "passive"))
      (node (ref "D6") (pin "2") (pinfunction "K_2") (pintype "passive"))
      (node (ref "D7") (pin "2") (pinfunction "K_2") (pintype "passive"))
      (node (ref "D8") (pin "2") (pinfunction "K_2") (pintype "passive"))
      (node (ref "P1") (pin "1") (pinfunction "1_1") (pintype "passive"))
      (node (ref "P10") (pin "4") (pinfunction "4_4") (pintype "passive"))
      (node (ref "P11") (pin "1") (pinfunction "1_1") (pintype "passive"))
      (node (ref "P12") (pin "4") (pinfunction "4_4") (pintype "passive"))
      (node (ref "P2") (pin "3") (pinfunction "3_3") (pintype "passive"))
      (node (ref "P4") (pin "2") (pinfunction "2_2") (pintype "passive"))
      (node (ref "P5") (pin "1") (pinfunction "1_1") (pintype "passive"))
      (node (ref "P6") (pin "1") (pinfunction "1_1") (pintype "passive"))
      (node (ref "P6") (pin "11") (pinfunction "11_11") (pintype "passive"))
      (node (ref "P6") (pin "13") (pinfunction "13_13") (pintype "passive"))
      (node (ref "P6") (pin "15") (pinfunction "15_15") (pintype "passive"))
      (node (ref "P6") (pin "17") (pinfunction "17_17") (pintype "passive"))
      (node (ref "P6") (pin "19") (pinfunction "19_19") (pintype "passive"))
      (node (ref "P6") (pin "3") (pinfunction "3_3") (pintype "passive"))
      (node (ref "P6") (pin "5") (pinfunction "5_5") (pintype "passive"))
      (node (ref "P6") (pin "7") (pinfunction "7_7") (pintype "passive"))
      (node (ref "P6") (pin "9") (pinfunction "9_9") (pintype "passive"))
      (node (ref "P7") (pin "10") (pinfunction "10_10") (pintype "passive"))
      (node (ref "P7") (pin "12") (pinfunction "12_12") (pintype "passive"))
      (node (ref "P7") (pin "14") (pinfunction "14_14") (pintype "passive"))
      (node (ref "P7") (pin "16") (pinfunction "16_16") (pintype "passive"))
      (node (ref "P7") (pin "18") (pinfunction "18_18") (pintype "passive"))
      (node (ref "P7") (pin "2") (pinfunction "2_2") (pintype "passive"))
      (node (ref "P7") (pin "4") (pinfunction "4_4") (pintype "passive"))
      (node (ref "P7") (pin "6") (pinfunction "6_6") (pintype "passive"))
      (node (ref "P7") (pin "8") (pinfunction "8_8") (pintype "passive"))
      (node (ref "P9") (pin "6") (pinfunction "6_6") (pintype "passive"))
      (node (ref "Q0") (pin "2") (pinfunction "2_2") (pintype "passive"))
      (node (ref "Q1") (pin "2") (pinfunction "2_2") (pintype "passive"))
      (node (ref "Q2") (pin "2") (pinfunction "2_2") (pintype "passive"))
      (node (ref "Q3") (pin "2") (pinfunction "2_2") (pintype "passive"))
      (node (ref "Q4") (pin "2") (pinfunction "2_2") (pintype "passive"))
      (node (ref "Q5") (pin "2") (pinfunction "2_2") (pintype "passive"))
      (node (ref "Q6") (pin "2") (pinfunction "2_2") (pintype "passive"))
      (node (ref "Q7") (pin "2") (pinfunction "2_2") (pintype "passive"))
      (node (ref "R29") (pin "1") (pinfunction "1_1") (pintype "passive"))
      (node (ref "R36") (pin "2") (pinfunction "2_2") (pintype "passive"))
      (node (ref "Rt") (pin "1") (pinfunction "1_1") (pintype "passive"))
      (node (ref "S2") (pin "1") (pinfunction "1_1") (pintype "passive"))
      (node (ref "U0") (pin "11") (pinfunction "GND_11") (pintype "power_in"))
      (node (ref "U0") (pin "32") (pinfunction "GND1_32") (pintype "power_in"))
      (node (ref "U0") (pin "62") (pinfunction "GND2_62") (pintype "power_in"))
      (node (ref "U0") (pin "81") (pinfunction "GND3_81") (pintype "power_in"))
      (node (ref "U0") (pin "99") (pinfunction "AGND_99") (pintype "power_in"))
      (node (ref "U1") (pin "2") (pinfunction "GND_2") (pintype "passive"))
      (node (ref "U2") (pin "2") (pinfunction "GND_2") (pintype "passive"))
      (node (ref "U3") (pin "2") (pinfunction "GND_2") (pintype "passive"))
      (node (ref "U4") (pin "1") (pinfunction "GND_1") (pintype "passive"))
      (node (ref "U5") (pin "4") (pinfunction "GND_4") (pintype "passive"))
      (node (ref "U5") (pin "5") (pinfunction "IN2+_5") (pintype "passive"))
      (node (ref "U5") (pin "6") (pinfunction "IN2-_6") (pintype "passive"))
    )
    (net (code "45") (name "Net-(D0-A)") (class "Default")
      (node (ref "D0") (pin "1") (pinfunction "A_1") (pintype "passive"))
      (node (ref "R11") (pin "1") (pinfunction "1_1") (pintype "passive"))
    )
    (net (code "46") (name "Net-(D1-A)") (class "Default")
      (node (ref "D1") (pin "1") (pinfunction "A_1") (pintype "passive"))
      (node (ref "R12") (pin "1") (pinfunction "1_1") (pintype "passive"))
    )
    (net (code "47") (name "Net-(D2-A)") (class "Default")
      (node (ref "D2") (pin "1") (pinfunction "A_1") (pintype "passive"))
      (node (ref "R13") (pin "1") (pinfunction "1_1") (pintype "passive"))
    )
    (net (code "48") (name "Net-(D3-A)") (class "Default")
      (node (ref "D3") (pin "1") (pinfunction "A_1") (pintype "passive"))
      (node (ref "R14") (pin "1") (pinfunction "1_1") (pintype "passive"))
    )
    (net (code "49") (name "Net-(D4-A)") (class "Default")
      (node (ref "D4") (pin "1") (pinfunction "A_1") (pintype "passive"))
      (node (ref "R15") (pin "1") (pinfunction "1_1") (pintype "passive"))
    )
    (net (code "50") (name "Net-(D5-A)") (class "Default")
      (node (ref "D5") (pin "1") (pinfunction "A_1") (pintype "passive"))
      (node (ref "R16") (pin "1") (pinfunction "1_1") (pintype "passive"))
    )
    (net (code "51") (name "Net-(D6-A)") (class "Default")
      (node (ref "D6") (pin "1") (pinfunction "A_1") (pintype "passive"))
      (node (ref "R17") (pin "1") (pinfunction "1_1") (pintype "passive"))
    )
    (net (code "52") (name "Net-(D7-A)") (class "Default")
      (node (ref "D7") (pin "1") (pinfunction "A_1") (pintype "passive"))
      (node (ref "R18") (pin "1") (pinfunction "1_1") (pintype "passive"))
    )
    (net (code "53") (name "Net-(D8-A)") (class "Default")
      (node (ref "D8") (pin "1") (pinfunction "A_1") (pintype "passive"))
      (node (ref "R32") (pin "1") (pinfunction "1_1") (pintype "passive"))
    )
    (net (code "54") (name "Net-(D9-A)") (class "Default")
      (node (ref "D9") (pin "1") (pinfunction "A_1") (pintype "passive"))
      (node (ref "P2") (pin "2") (pinfunction "2_2") (pintype "passive"))
    )
    (net (code "55") (name "Net-(D9-K)") (class "Default")
      (node (ref "D9") (pin "2") (pinfunction "K_2") (pintype "passive"))
      (node (ref "F") (pin "1") (pinfunction "1_1") (pintype "passive"))
    )
    (net (code "56") (name "Net-(D10-A)") (class "Default")
      (node (ref "D10") (pin "1") (pinfunction "A_1") (pintype "passive"))
      (node (ref "R31") (pin "2") (pinfunction "2_2") (pintype "passive"))
    )
    (net (code "57") (name "Net-(D11-A)") (class "Default")
      (node (ref "C8") (pin "2") (pinfunction "2_2") (pintype "passive"))
      (node (ref "C9") (pin "1") (pinfunction "1_1") (pintype "passive"))
      (node (ref "D11") (pin "1") (pinfunction "A_1") (pintype "passive"))
      (node (ref "U1") (pin "3") (pinfunction "Vout_3") (pintype "passive"))
    )
    (net (code "58") (name "Net-(D12-A)") (class "Default")
      (node (ref "D12") (pin "1") (pinfunction "A_1") (pintype "passive"))
      (node (ref "R38") (pin "1") (pinfunction "1_1") (pintype "passive"))
    )
    (net (code "59") (name "Net-(D13-A)") (class "Default")
      (node (ref "D13") (pin "1") (pinfunction "A_1") (pintype "passive"))
      (node (ref "R39") (pin "1") (pinfunction "1_1") (pintype "passive"))
    )
    (net (code "60") (name "Net-(D14-A)") (class "Default")
      (node (ref "D14") (pin "1") (pinfunction "A_1") (pintype "passive"))
      (node (ref "R40") (pin "1") (pinfunction "1_1") (pintype "passive"))
    )
    (net (code "61") (name "Net-(D15-A)") (class "Default")
      (node (ref "D15") (pin "1") (pinfunction "A_1") (pintype "passive"))
      (node (ref "R41") (pin "1") (pinfunction "1_1") (pintype "passive"))
    )
    (net (code "62") (name "Net-(D16-A)") (class "Default")
      (node (ref "D16") (pin "1") (pinfunction "A_1") (pintype "passive"))
      (node (ref "R42") (pin "1") (pinfunction "1_1") (pintype "passive"))
    )
    (net (code "63") (name "Net-(D17-A)") (class "Default")
      (node (ref "D17") (pin "1") (pinfunction "A_1") (pintype "passive"))
      (node (ref "R43") (pin "1") (pinfunction "1_1") (pintype "passive"))
    )
    (net (code "64") (name "Net-(D18-A)") (class "Default")
      (node (ref "D18") (pin "1") (pinfunction "A_1") (pintype "passive"))
      (node (ref "R44") (pin "1") (pinfunction "1_1") (pintype "passive"))
    )
    (net (code "65") (name "Net-(D19-A)") (class "Default")
      (node (ref "D19") (pin "1") (pinfunction "A_1") (pintype "passive"))
      (node (ref "R45") (pin "1") (pinfunction "1_1") (pintype "passive"))
    )
    (net (code "66") (name "Net-(P7-Pad1)") (class "Default")
      (node (ref "P7") (pin "1") (pinfunction "1_1") (pintype "passive"))
      (node (ref "P8") (pin "2") (pinfunction "2_2") (pintype "passive"))
    )
    (net (code "67") (name "Net-(P7-Pad3)") (class "Default")
      (node (ref "P7") (pin "3") (pinfunction "3_3") (pintype "passive"))
      (node (ref "P8") (pin "4") (pinfunction "4_4") (pintype "passive"))
    )
    (net (code "68") (name "Net-(P7-Pad5)") (class "Default")
      (node (ref "P7") (pin "5") (pinfunction "5_5") (pintype "passive"))
      (node (ref "P8") (pin "6") (pinfunction "6_6") (pintype "passive"))
    )
    (net (code "69") (name "Net-(P7-Pad7)") (class "Default")
      (node (ref "P7") (pin "7") (pinfunction "7_7") (pintype "passive"))
      (node (ref "P8") (pin "8") (pinfunction "8_8") (pintype "passive"))
    )
    (net (code "70") (name "Net-(P7-Pad9)") (class "Default")
      (node (ref "P7") (pin "9") (pinfunction "9_9") (pintype "passive"))
      (node (ref "P8") (pin "10") (pinfunction "10_10") (pintype "passive"))
    )
    (net (code "71") (name "Net-(P7-Pad11)") (class "Default")
      (node (ref "P7") (pin "11") (pinfunction "11_11") (pintype "passive"))
      (node (ref "P8") (pin "12") (pinfunction "12_12") (pintype "passive"))
    )
    (net (code "72") (name "Net-(P7-Pad13)") (class "Default")
      (node (ref "P7") (pin "13") (pinfunction "13_13") (pintype "passive"))
      (node (ref "P8") (pin "14") (pinfunction "14_14") (pintype "passive"))
    )
    (net (code "73") (name "Net-(P7-Pad15)") (class "Default")
      (node (ref "P7") (pin "15") (pinfunction "15_15") (pintype "passive"))
      (node (ref "P8") (pin "16") (pinfunction "16_16") (pintype "passive"))
    )
    (net (code "74") (name "Net-(P10-Pad5)") (class "Default")
      (node (ref "P10") (pin "5") (pinfunction "5_5") (pintype "passive"))
      (node (ref "P3") (pin "2") (pinfunction "2_2") (pintype "passive"))
    )
    (net (code "75") (name "Net-(P10-Pad7)") (class "Default")
      (node (ref "P10") (pin "7") (pinfunction "7_7") (pintype "passive"))
      (node (ref "P3") (pin "4") (pinfunction "4_4") (pintype "passive"))
    )
    (net (code "76") (name "Net-(P10-Pad9)") (class "Default")
      (node (ref "P10") (pin "9") (pinfunction "9_9") (pintype "passive"))
      (node (ref "P3") (pin "6") (pinfunction "6_6") (pintype "passive"))
    )
    (net (code "77") (name "Net-(P10-Pad11)") (class "Default")
      (node (ref "P10") (pin "11") (pinfunction "11_11") (pintype "passive"))
      (node (ref "P3") (pin "8") (pinfunction "8_8") (pintype "passive"))
    )
    (net (code "78") (name "Net-(P10-Pad13)") (class "Default")
      (node (ref "P10") (pin "13") (pinfunction "13_13") (pintype "passive"))
      (node (ref "P3") (pin "10") (pinfunction "10_10") (pintype "passive"))
    )
    (net (code "79") (name "Net-(P10-Pad15)") (class "Default")
      (node (ref "P10") (pin "15") (pinfunction "15_15") (pintype "passive"))
      (node (ref "P3") (pin "12") (pinfunction "12_12") (pintype "passive"))
    )
    (net (code "80") (name "Net-(P10-Pad17)") (class "Default")
      (node (ref "P10") (pin "17") (pinfunction "17_17") (pintype "passive"))
      (node (ref "P3") (pin "14") (pinfunction "14_14") (pintype "passive"))
    )
    (net (code "81") (name "Net-(P10-Pad19)") (class "Default")
      (node (ref "P10") (pin "19") (pinfunction "19_19") (pintype "passive"))
      (node (ref "P3") (pin "16") (pinfunction "16_16") (pintype "passive"))
    )
    (net (code "82") (name "Net-(Q0-Pad1)") (class "Default")
      (node (ref "Q0") (pin "1") (pinfunction "1_1") (pintype "passive"))
      (node (ref "R19") (pin "2") (pinfunction "2_2") (pintype "passive"))
    )
    (net (code "83") (name "Net-(Q0-Pad3)") (class "Default")
      (node (ref "Q0") (pin "3") (pinfunction "3_3") (pintype "passive"))
      (node (ref "U6") (pin "2") (pinfunction "2_2") (pintype "passive"))
    )
    (net (code "84") (name "Net-(Q1-Pad1)") (class "Default")
      (node (ref "Q1") (pin "1") (pinfunction "1_1") (pintype "passive"))
      (node (ref "R20") (pin "2") (pinfunction "2_2") (pintype "passive"))
    )
    (net (code "85") (name "Net-(Q1-Pad3)") (class "Default")
      (node (ref "Q1") (pin "3") (pinfunction "3_3") (pintype "passive"))
      (node (ref "U7") (pin "2") (pinfunction "2_2") (pintype "passive"))
    )
    (net (code "86") (name "Net-(Q2-Pad1)") (class "Default")
      (node (ref "Q2") (pin "1") (pinfunction "1_1") (pintype "passive"))
      (node (ref "R21") (pin "2") (pinfunction "2_2") (pintype "passive"))
    )
    (net (code "87") (name "Net-(Q2-Pad3)") (class "Default")
      (node (ref "Q2") (pin "3") (pinfunction "3_3") (pintype "passive"))
      (node (ref "U8") (pin "2") (pinfunction "2_2") (pintype "passive"))
    )
    (net (code "88") (name "Net-(Q3-Pad1)") (class "Default")
      (node (ref "Q3") (pin "1") (pinfunction "1_1") (pintype "passive"))
      (node (ref "R22") (pin "2") (pinfunction "2_2") (pintype "passive"))
    )
    (net (code "89") (name "Net-(Q3-Pad3)") (class "Default")
      (node (ref "Q3") (pin "3") (pinfunction "3_3") (pintype "passive"))
      (node (ref "U9") (pin "2") (pinfunction "2_2") (pintype "passive"))
    )
    (net (code "90") (name "Net-(Q4-Pad1)") (class "Default")
      (node (ref "Q4") (pin "1") (pinfunction "1_1") (pintype "passive"))
      (node (ref "R23") (pin "2") (pinfunction "2_2") (pintype "passive"))
    )
    (net (code "91") (name "Net-(Q4-Pad3)") (class "Default")
      (node (ref "Q4") (pin "3") (pinfunction "3_3") (pintype "passive"))
      (node (ref "U10") (pin "2") (pinfunction "2_2") (pintype "passive"))
    )
    (net (code "92") (name "Net-(Q5-Pad1)") (class "Default")
      (node (ref "Q5") (pin "1") (pinfunction "1_1") (pintype "passive"))
      (node (ref "R24") (pin "2") (pinfunction "2_2") (pintype "passive"))
    )
    (net (code "93") (name "Net-(Q5-Pad3)") (class "Default")
      (node (ref "Q5") (pin "3") (pinfunction "3_3") (pintype "passive"))
      (node (ref "U11") (pin "2") (pinfunction "2_2") (pintype "passive"))
    )
    (net (code "94") (name "Net-(Q6-Pad1)") (class "Default")
      (node (ref "Q6") (pin "1") (pinfunction "1_1") (pintype "passive"))
      (node (ref "R25") (pin "2") (pinfunction "2_2") (pintype "passive"))
    )
    (net (code "95") (name "Net-(Q6-Pad3)") (class "Default")
      (node (ref "Q6") (pin "3") (pinfunction "3_3") (pintype "passive"))
      (node (ref "U12") (pin "2") (pinfunction "2_2") (pintype "passive"))
    )
    (net (code "96") (name "Net-(Q7-Pad1)") (class "Default")
      (node (ref "Q7") (pin "1") (pinfunction "1_1") (pintype "passive"))
      (node (ref "R26") (pin "2") (pinfunction "2_2") (pintype "passive"))
    )
    (net (code "97") (name "Net-(Q7-Pad3)") (class "Default")
      (node (ref "Q7") (pin "3") (pinfunction "3_3") (pintype "passive"))
      (node (ref "U13") (pin "2") (pinfunction "2_2") (pintype "passive"))
    )
    (net (code "98") (name "Net-(R3-Pad2)") (class "Default")
      (node (ref "R3") (pin "2") (pinfunction "2_2") (pintype "passive"))
      (node (ref "U6") (pin "1") (pinfunction "1_1") (pintype "passive"))
    )
    (net (code "99") (name "Net-(R4-Pad2)") (class "Default")
      (node (ref "R4") (pin "2") (pinfunction "2_2") (pintype "passive"))
      (node (ref "U7") (pin "1") (pinfunction "1_1") (pintype "passive"))
    )
    (net (code "100") (name "Net-(R5-Pad2)") (class "Default")
      (node (ref "R5") (pin "2") (pinfunction "2_2") (pintype "passive"))
      (node (ref "U8") (pin "1") (pinfunction "1_1") (pintype "passive"))
    )
    (net (code "101") (name "Net-(R6-Pad2)") (class "Default")
      (node (ref "R6") (pin "2") (pinfunction "2_2") (pintype "passive"))
      (node (ref "U9") (pin "1") (pinfunction "1_1") (pintype "passive"))
    )
    (net (code "102") (name "Net-(R7-Pad2)") (class "Default")
      (node (ref "R7") (pin "2") (pinfunction "2_2") (pintype "passive"))
      (node (ref "U10") (pin "1") (pinfunction "1_1") (pintype "passive"))
    )
    (net (code "103") (name "Net-(R8-Pad2)") (class "Default")
      (node (ref "R8") (pin "2") (pinfunction "2_2") (pintype "passive"))
      (node (ref "U11") (pin "1") (pinfunction "1_1") (pintype "passive"))
    )
    (net (code "104") (name "Net-(R9-Pad2)") (class "Default")
      (node (ref "R9") (pin "2") (pinfunction "2_2") (pintype "passive"))
      (node (ref "U12") (pin "1") (pinfunction "1_1") (pintype "passive"))
    )
    (net (code "105") (name "Net-(R10-Pad2)") (class "Default")
      (node (ref "R10") (pin "2") (pinfunction "2_2") (pintype "passive"))
      (node (ref "U13") (pin "1") (pinfunction "1_1") (pintype "passive"))
    )
    (net (code "106") (name "Net-(R29-Pad2)") (class "Default")
      (node (ref "R29") (pin "2") (pinfunction "2_2") (pintype "passive"))
      (node (ref "R37") (pin "2") (pinfunction "2_2") (pintype "passive"))
    )
    (net (code "107") (name "Net-(S1-NO)") (class "Default")
      (node (ref "F") (pin "2") (pinfunction "2_2") (pintype "passive"))
      (node (ref "S1") (pin "2") (pinfunction "NO_2") (pintype "passive"))
    )
    (net (code "108") (name "Net-(U0-AVCC)") (class "Default")
      (node (ref "C7") (pin "2") (pintype "passive"))
      (node (ref "L1") (pin "1") (pinfunction "1_1") (pintype "passive"))
      (node (ref "U0") (pin "100") (pinfunction "AVCC_100") (pintype "power_in"))
    )
    (net (code "109") (name "Net-(U5-IN1+)") (class "Default")
      (node (ref "R30") (pin "1") (pinfunction "1_1") (pintype "passive"))
      (node (ref "U5") (pin "3") (pinfunction "IN1+_3") (pintype "passive"))
    )
    (net (code "110") (name "Net-(U5-IN1-)") (class "Default")
      (node (ref "P11") (pin "2") (pinfunction "2_2") (pintype "passive"))
      (node (ref "R28") (pin "2") (pinfunction "2_2") (pintype "passive"))
      (node (ref "R37") (pin "1") (pinfunction "1_1") (pintype "passive"))
      (node (ref "U5") (pin "2") (pinfunction "IN1-_2") (pintype "passive"))
    )
    (net (code "111") (name "Net-(U5-OUT1)") (class "Default")
      (node (ref "R31") (pin "1") (pinfunction "1_1") (pintype "passive"))
      (node (ref "U5") (pin "1") (pinfunction "OUT1_1") (pintype "passive"))
    )
    (net (code "112") (name "Vc") (class "Default")
      (node (ref "C14") (pin "2") (pinfunction "2_2") (pintype "passive"))
      (node (ref "C15") (pin "1") (pinfunction "1_1") (pintype "passive"))
      (node (ref "C18") (pin "2") (pinfunction "2_2") (pintype "passive"))
      (node (ref "P6") (pin "20") (pinfunction "20_20") (pintype "passive"))
      (node (ref "R28") (pin "1") (pinfunction "1_1") (pintype "passive"))
      (node (ref "R32") (pin "2") (pinfunction "2_2") (pintype "passive"))
      (node (ref "R35") (pin "1") (pinfunction "1_1") (pintype "passive"))
      (node (ref "S1") (pin "1") (pinfunction "COMMON_1") (pintype "passive"))
      (node (ref "U10") (pin "4") (pinfunction "4_4") (pintype "passive"))
      (node (ref "U11") (pin "4") (pinfunction "4_4") (pintype "passive"))
      (node (ref "U12") (pin "4") (pinfunction "4_4") (pintype "passive"))
      (node (ref "U13") (pin "4") (pinfunction "4_4") (pintype "passive"))
      (node (ref "U2") (pin "1") (pinfunction "Vin_1") (pintype "passive"))
      (node (ref "U3") (pin "1") (pinfunction "Vin_1") (pintype "passive"))
      (node (ref "U5") (pin "8") (pinfunction "VCC_8") (pintype "passive"))
      (node (ref "U6") (pin "4") (pinfunction "4_4") (pintype "passive"))
      (node (ref "U7") (pin "4") (pinfunction "4_4") (pintype "passive"))
      (node (ref "U8") (pin "4") (pinfunction "4_4") (pintype "passive"))
      (node (ref "U9") (pin "4") (pinfunction "4_4") (pintype "passive"))
    )
    (net (code "113") (name "unconnected-(P6-Pad18)") (class "Default")
      (node (ref "P6") (pin "18") (pinfunction "18_18") (pintype "passive"))
    )
    (net (code "114") (name "unconnected-(P7-Pad17)") (class "Default")
      (node (ref "P7") (pin "17") (pinfunction "17_17") (pintype "passive"))
    )
    (net (code "115") (name "unconnected-(P7-Pad19)") (class "Default")
      (node (ref "P7") (pin "19") (pinfunction "19_19") (pintype "passive"))
    )
    (net (code "116") (name "unconnected-(P7-Pad20)") (class "Default")
      (node (ref "P7") (pin "20") (pinfunction "20_20") (pintype "passive"))
    )
    (net (code "117") (name "unconnected-(P10-Pad6)") (class "Default")
      (node (ref "P10") (pin "6") (pinfunction "6_6") (pintype "passive"))
    )
    (net (code "118") (name "unconnected-(P10-Pad8)") (class "Default")
      (node (ref "P10") (pin "8") (pinfunction "8_8") (pintype "passive"))
    )
    (net (code "119") (name "unconnected-(P10-Pad10)") (class "Default")
      (node (ref "P10") (pin "10") (pinfunction "10_10") (pintype "passive"))
    )
    (net (code "120") (name "unconnected-(P10-Pad12)") (class "Default")
      (node (ref "P10") (pin "12") (pinfunction "12_12") (pintype "passive"))
    )
    (net (code "121") (name "unconnected-(P10-Pad14)") (class "Default")
      (node (ref "P10") (pin "14") (pinfunction "14_14") (pintype "passive"))
    )
    (net (code "122") (name "unconnected-(P10-Pad16)") (class "Default")
      (node (ref "P10") (pin "16") (pinfunction "16_16") (pintype "passive"))
    )
    (net (code "123") (name "unconnected-(P10-Pad18)") (class "Default")
      (node (ref "P10") (pin "18") (pinfunction "18_18") (pintype "passive"))
    )
    (net (code "124") (name "unconnected-(P10-Pad20)") (class "Default")
      (node (ref "P10") (pin "20") (pinfunction "20_20") (pintype "passive"))
    )
    (net (code "125") (name "unconnected-(U0-(A8)PC0-Pad53)") (class "Default")
      (node (ref "U0") (pin "53") (pinfunction "(A8)PC0_53") (pintype "passive"))
    )
    (net (code "126") (name "unconnected-(U0-(A9)PC1-Pad54)") (class "Default")
      (node (ref "U0") (pin "54") (pinfunction "(A9)PC1_54") (pintype "passive"))
    )
    (net (code "127") (name "unconnected-(U0-(A10)PC2-Pad55)") (class "Default")
      (node (ref "U0") (pin "55") (pinfunction "(A10)PC2_55") (pintype "passive"))
    )
    (net (code "128") (name "unconnected-(U0-(A11)PC3-Pad56)") (class "Default")
      (node (ref "U0") (pin "56") (pinfunction "(A11)PC3_56") (pintype "passive"))
    )
    (net (code "129") (name "unconnected-(U0-(A12)PC4-Pad57)") (class "Default")
      (node (ref "U0") (pin "57") (pinfunction "(A12)PC4_57") (pintype "passive"))
    )
    (net (code "130") (name "unconnected-(U0-(A13)PC5-Pad58)") (class "Default")
      (node (ref "U0") (pin "58") (pinfunction "(A13)PC5_58") (pintype "passive"))
    )
    (net (code "131") (name "unconnected-(U0-(A14)PC6-Pad59)") (class "Default")
      (node (ref "U0") (pin "59") (pinfunction "(A14)PC6_59") (pintype "passive"))
    )
    (net (code "132") (name "unconnected-(U0-(A15)PC7-Pad60)") (class "Default")
      (node (ref "U0") (pin "60") (pinfunction "(A15)PC7_60") (pintype "passive"))
    )
    (net (code "133") (name "unconnected-(U0-(AD0)PA0-Pad78)") (class "Default")
      (node (ref "U0") (pin "78") (pinfunction "(AD0)PA0_78") (pintype "passive"))
    )
    (net (code "134") (name "unconnected-(U0-(AD1)PA1-Pad77)") (class "Default")
      (node (ref "U0") (pin "77") (pinfunction "(AD1)PA1_77") (pintype "passive"))
    )
    (net (code "135") (name "unconnected-(U0-(AD2)PA2-Pad76)") (class "Default")
      (node (ref "U0") (pin "76") (pinfunction "(AD2)PA2_76") (pintype "passive"))
    )
    (net (code "136") (name "unconnected-(U0-(AD3)PA3-Pad75)") (class "Default")
      (node (ref "U0") (pin "75") (pinfunction "(AD3)PA3_75") (pintype "passive"))
    )
    (net (code "137") (name "unconnected-(U0-(AD4)PA4-Pad74)") (class "Default")
      (node (ref "U0") (pin "74") (pinfunction "(AD4)PA4_74") (pintype "passive"))
    )
    (net (code "138") (name "unconnected-(U0-(AD5)PA5-Pad73)") (class "Default")
      (node (ref "U0") (pin "73") (pinfunction "(AD5)PA5_73") (pintype "passive"))
    )
    (net (code "139") (name "unconnected-(U0-(AD6)PA6-Pad72)") (class "Default")
      (node (ref "U0") (pin "72") (pinfunction "(AD6)PA6_72") (pintype "passive"))
    )
    (net (code "140") (name "unconnected-(U0-(AD7)PA7-Pad71)") (class "Default")
      (node (ref "U0") (pin "71") (pinfunction "(AD7)PA7_71") (pintype "passive"))
    )
    (net (code "141") (name "unconnected-(U0-(ALE)PG2-Pad70)") (class "Default")
      (node (ref "U0") (pin "70") (pinfunction "(ALE)PG2_70") (pintype "passive"))
    )
    (net (code "142") (name "unconnected-(U0-(CLKO{slash}ICP3{slash}INT7)PE7-Pad9)") (class "Default")
      (node (ref "U0") (pin "9") (pinfunction "(CLKO/ICP3/INT7)PE7_9") (pintype "passive"))
    )
    (net (code "143") (name "unconnected-(U0-(ICP1)PD4-Pad47)") (class "Default")
      (node (ref "U0") (pin "47") (pinfunction "(ICP1)PD4_47") (pintype "passive"))
    )
    (net (code "144") (name "unconnected-(U0-(OC0A{slash}OC1C{slash}PCINT7)PB7-Pad26)") (class "Default")
      (node (ref "U0") (pin "26") (pinfunction "(OC0A/OC1C/PCINT7)PB7_26") (pintype "passive"))
    )
    (net (code "145") (name "unconnected-(U0-(OC0B)PG5-Pad1)") (class "Default")
      (node (ref "U0") (pin "1") (pinfunction "(OC0B)PG5_1") (pintype "passive"))
    )
    (net (code "146") (name "unconnected-(U0-(OC1A{slash}PCINT5)PB5-Pad24)") (class "Default")
      (node (ref "U0") (pin "24") (pinfunction "(OC1A/PCINT5)PB5_24") (pintype "passive"))
    )
    (net (code "147") (name "unconnected-(U0-(OC1B{slash}PCINT6)PB6-Pad25)") (class "Default")
      (node (ref "U0") (pin "25") (pinfunction "(OC1B/PCINT6)PB6_25") (pintype "passive"))
    )
    (net (code "148") (name "unconnected-(U0-(OC2A{slash}PCINT4)PB4-Pad23)") (class "Default")
      (node (ref "U0") (pin "23") (pinfunction "(OC2A/PCINT4)PB4_23") (pintype "passive"))
    )
    (net (code "149") (name "unconnected-(U0-(OC3A{slash}AIN1)PE3-Pad5)") (class "Default")
      (node (ref "U0") (pin "5") (pinfunction "(OC3A/AIN1)PE3_5") (pintype "passive"))
    )
    (net (code "150") (name "unconnected-(U0-(OC3B{slash}INT4)PE4-Pad6)") (class "Default")
      (node (ref "U0") (pin "6") (pinfunction "(OC3B/INT4)PE4_6") (pintype "passive"))
    )
    (net (code "151") (name "unconnected-(U0-(OC3C{slash}INT5)PE5-Pad7)") (class "Default")
      (node (ref "U0") (pin "7") (pinfunction "(OC3C/INT5)PE5_7") (pintype "passive"))
    )
    (net (code "152") (name "unconnected-(U0-(RD)PG1-Pad52)") (class "Default")
      (node (ref "U0") (pin "52") (pinfunction "(RD)PG1_52") (pintype "passive"))
    )
    (net (code "153") (name "unconnected-(U0-(RXD1{slash}INT2)PD2-Pad45)") (class "Default")
      (node (ref "U0") (pin "45") (pinfunction "(RXD1/INT2)PD2_45") (pintype "passive"))
    )
    (net (code "154") (name "unconnected-(U0-(SS{slash}PCINT0)PB0-Pad19)") (class "Default")
      (node (ref "U0") (pin "19") (pinfunction "(SS/PCINT0)PB0_19") (pintype "passive"))
    )
    (net (code "155") (name "unconnected-(U0-(T0)PD7-Pad50)") (class "Default")
      (node (ref "U0") (pin "50") (pinfunction "(T0)PD7_50") (pintype "passive"))
    )
    (net (code "156") (name "unconnected-(U0-(T1)PD6-Pad49)") (class "Default")
      (node (ref "U0") (pin "49") (pinfunction "(T1)PD6_49") (pintype "passive"))
    )
    (net (code "157") (name "unconnected-(U0-(T3{slash}INT6)PE6-Pad8)") (class "Default")
      (node (ref "U0") (pin "8") (pinfunction "(T3/INT6)PE6_8") (pintype "passive"))
    )
    (net (code "158") (name "unconnected-(U0-(TOSC1)PG4-Pad29)") (class "Default")
      (node (ref "U0") (pin "29") (pinfunction "(TOSC1)PG4_29") (pintype "passive"))
    )
    (net (code "159") (name "unconnected-(U0-(TOSC2)PG3-Pad28)") (class "Default")
      (node (ref "U0") (pin "28") (pinfunction "(TOSC2)PG3_28") (pintype "passive"))
    )
    (net (code "160") (name "unconnected-(U0-(TXD1{slash}INT3)PD3-Pad46)") (class "Default")
      (node (ref "U0") (pin "46") (pinfunction "(TXD1/INT3)PD3_46") (pintype "passive"))
    )
    (net (code "161") (name "unconnected-(U0-(WR)PG0-Pad51)") (class "Default")
      (node (ref "U0") (pin "51") (pinfunction "(WR)PG0_51") (pintype "passive"))
    )
    (net (code "162") (name "unconnected-(U0-(XCK0{slash}AIN0)PE2-Pad4)") (class "Default")
      (node (ref "U0") (pin "4") (pinfunction "(XCK0/AIN0)PE2_4") (pintype "passive"))
    )
    (net (code "163") (name "unconnected-(U0-(XCK1)PD5-Pad48)") (class "Default")
      (node (ref "U0") (pin "48") (pinfunction "(XCK1)PD5_48") (pintype "passive"))
    )
    (net (code "164") (name "unconnected-(U0-PH0(RXD2)-Pad12)") (class "Default")
      (node (ref "U0") (pin "12") (pinfunction "PH0(RXD2)_12") (pintype "passive"))
    )
    (net (code "165") (name "unconnected-(U0-PH1(TXD2)-Pad13)") (class "Default")
      (node (ref "U0") (pin "13") (pinfunction "PH1(TXD2)_13") (pintype "passive"))
    )
    (net (code "166") (name "unconnected-(U0-PH2(XCK2)-Pad14)") (class "Default")
      (node (ref "U0") (pin "14") (pinfunction "PH2(XCK2)_14") (pintype "passive"))
    )
    (net (code "167") (name "unconnected-(U0-PH3(OC4A)-Pad15)") (class "Default")
      (node (ref "U0") (pin "15") (pinfunction "PH3(OC4A)_15") (pintype "passive"))
    )
    (net (code "168") (name "unconnected-(U0-PH4(OC4B)-Pad16)") (class "Default")
      (node (ref "U0") (pin "16") (pinfunction "PH4(OC4B)_16") (pintype "passive"))
    )
    (net (code "169") (name "unconnected-(U0-PH5(OC4C)-Pad17)") (class "Default")
      (node (ref "U0") (pin "17") (pinfunction "PH5(OC4C)_17") (pintype "passive"))
    )
    (net (code "170") (name "unconnected-(U0-PH6(OC2B)-Pad18)") (class "Default")
      (node (ref "U0") (pin "18") (pinfunction "PH6(OC2B)_18") (pintype "passive"))
    )
    (net (code "171") (name "unconnected-(U0-PH7(T4)-Pad27)") (class "Default")
      (node (ref "U0") (pin "27") (pinfunction "PH7(T4)_27") (pintype "passive"))
    )
    (net (code "172") (name "unconnected-(U0-PJ0(RXD3{slash}PCINT9)-Pad63)") (class "Default")
      (node (ref "U0") (pin "63") (pinfunction "PJ0(RXD3/PCINT9)_63") (pintype "passive"))
    )
    (net (code "173") (name "unconnected-(U0-PJ1(TXD3{slash}PCINT10)-Pad64)") (class "Default")
      (node (ref "U0") (pin "64") (pinfunction "PJ1(TXD3/PCINT10)_64") (pintype "passive"))
    )
    (net (code "174") (name "unconnected-(U0-PJ2(XCK3{slash}PCINT11)-Pad65)") (class "Default")
      (node (ref "U0") (pin "65") (pinfunction "PJ2(XCK3/PCINT11)_65") (pintype "passive"))
    )
    (net (code "175") (name "unconnected-(U0-PJ3(PCINT12)-Pad66)") (class "Default")
      (node (ref "U0") (pin "66") (pinfunction "PJ3(PCINT12)_66") (pintype "passive"))
    )
    (net (code "176") (name "unconnected-(U0-PJ4(PCINT13)-Pad67)") (class "Default")
      (node (ref "U0") (pin "67") (pinfunction "PJ4(PCINT13)_67") (pintype "passive"))
    )
    (net (code "177") (name "unconnected-(U0-PJ5(PCINT14)-Pad68)") (class "Default")
      (node (ref "U0") (pin "68") (pinfunction "PJ5(PCINT14)_68") (pintype "passive"))
    )
    (net (code "178") (name "unconnected-(U0-PJ6(PCINT15)-Pad69)") (class "Default")
      (node (ref "U0") (pin "69") (pinfunction "PJ6(PCINT15)_69") (pintype "passive"))
    )
    (net (code "179") (name "unconnected-(U0-PJ7-Pad79)") (class "Default")
      (node (ref "U0") (pin "79") (pinfunction "PJ7_79") (pintype "passive"))
    )
    (net (code "180") (name "unconnected-(U0-PK1(ADC9{slash}PCINT17)-Pad88)") (class "Default")
      (node (ref "U0") (pin "88") (pinfunction "PK1(ADC9/PCINT17)_88") (pintype "passive"))
    )
    (net (code "181") (name "unconnected-(U0-PK2(ADC10{slash}PCINT18)-Pad87)") (class "Default")
      (node (ref "U0") (pin "87") (pinfunction "PK2(ADC10/PCINT18)_87") (pintype "passive"))
    )
    (net (code "182") (name "unconnected-(U0-PK3(ADC11{slash}PCINT19)-Pad86)") (class "Default")
      (node (ref "U0") (pin "86") (pinfunction "PK3(ADC11/PCINT19)_86") (pintype "passive"))
    )
    (net (code "183") (name "unconnected-(U0-PK4(ADC12{slash}PCINT20)-Pad85)") (class "Default")
      (node (ref "U0") (pin "85") (pinfunction "PK4(ADC12/PCINT20)_85") (pintype "passive"))
    )
    (net (code "184") (name "unconnected-(U0-PK5(ADC13{slash}PCINT21)-Pad84)") (class "Default")
      (node (ref "U0") (pin "84") (pinfunction "PK5(ADC13/PCINT21)_84") (pintype "passive"))
    )
    (net (code "185") (name "unconnected-(U0-PK6(ADC14{slash}PCINT22)-Pad83)") (class "Default")
      (node (ref "U0") (pin "83") (pinfunction "PK6(ADC14/PCINT22)_83") (pintype "passive"))
    )
    (net (code "186") (name "unconnected-(U0-PK7(ADC15{slash}PCINT23)-Pad82)") (class "Default")
      (node (ref "U0") (pin "82") (pinfunction "PK7(ADC15/PCINT23)_82") (pintype "passive"))
    )
    (net (code "187") (name "unconnected-(U0-PL0(ICP4)-Pad35)") (class "Default")
      (node (ref "U0") (pin "35") (pinfunction "PL0(ICP4)_35") (pintype "passive"))
    )
    (net (code "188") (name "unconnected-(U0-PL1(ICP5)-Pad36)") (class "Default")
      (node (ref "U0") (pin "36") (pinfunction "PL1(ICP5)_36") (pintype "passive"))
    )
    (net (code "189") (name "unconnected-(U0-PL2(T5)-Pad37)") (class "Default")
      (node (ref "U0") (pin "37") (pinfunction "PL2(T5)_37") (pintype "passive"))
    )
    (net (code "190") (name "unconnected-(U0-PL3(OC5A)-Pad38)") (class "Default")
      (node (ref "U0") (pin "38") (pinfunction "PL3(OC5A)_38") (pintype "passive"))
    )
    (net (code "191") (name "unconnected-(U0-PL4(OC5B)-Pad39)") (class "Default")
      (node (ref "U0") (pin "39") (pinfunction "PL4(OC5B)_39") (pintype "passive"))
    )
    (net (code "192") (name "unconnected-(U0-PL5(OC5C)-Pad40)") (class "Default")
      (node (ref "U0") (pin "40") (pinfunction "PL5(OC5C)_40") (pintype "passive"))
    )
    (net (code "193") (name "unconnected-(U0-PL6-Pad41)") (class "Default")
      (node (ref "U0") (pin "41") (pinfunction "PL6_41") (pintype "passive"))
    )
    (net (code "194") (name "unconnected-(U0-PL7-Pad42)") (class "Default")
      (node (ref "U0") (pin "42") (pinfunction "PL7_42") (pintype "passive"))
    )
    (net (code "195") (name "unconnected-(U5-OUT2-Pad7)") (class "Default")
      (node (ref "U5") (pin "7") (pinfunction "OUT2_7") (pintype "passive"))
    )
  )
)
